# ir.net
KiCad netlist of a schematic drawn in EAGLE
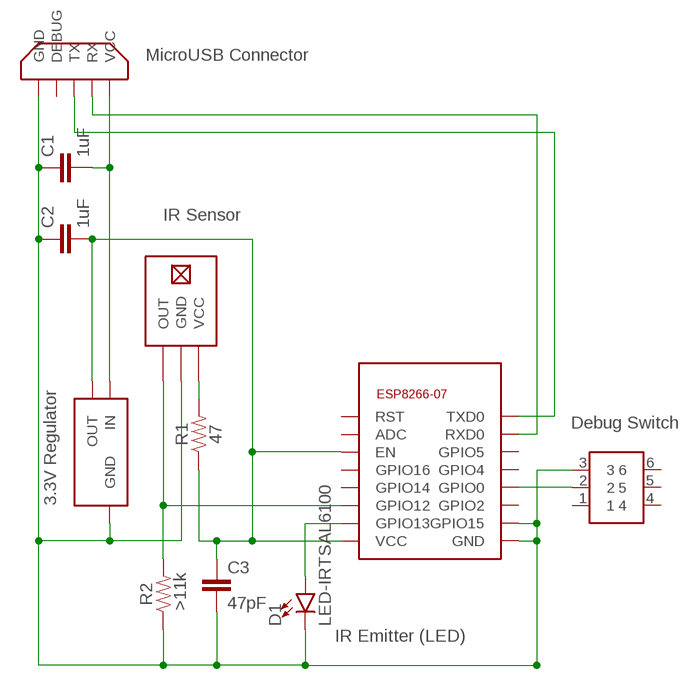
[diagram p0: schematic, sheet 1]

(export (version "E")
  (design (tool "Eeschema 10.0.6"))
  (components
    (comp (ref "C1")
      (value "1uF")
      (footprint "eagle-import:0805")
      (libsource (lib "eagle-import") (part "0.33UF/330NF-0805-50V-10%"))
    )
    (comp (ref "C2")
      (value "1uF")
      (footprint "eagle-import:0805")
      (libsource (lib "eagle-import") (part "0.33UF/330NF-0805-50V-10%"))
    )
    (comp (ref "C3")
      (value "47pF")
      (footprint "eagle-import:0805")
      (libsource (lib "eagle-import") (part "0.33UF/330NF-0805-50V-10%"))
    )
    (comp (ref "D1")
      (value "LED-IRTSAL6100")
      (footprint "eagle-import:LED_5MM")
      (libsource (lib "eagle-import") (part "LED-IRTSAL6100"))
    )
    (comp (ref "R1")
      (value "47")
      (footprint "eagle-import:0805")
      (libsource (lib "eagle-import") (part "RESISTOR0805"))
    )
    (comp (ref "R2")
      (value ">11k")
      (footprint "eagle-import:0805")
      (libsource (lib "eagle-import") (part "RESISTOR0805"))
    )
    (comp (ref "U$1")
      (value "AX-1838HSHORIZ")
      (footprint "eagle-import:AX-1838HS-HORIZ")
      (libsource (lib "eagle-import") (part "AX-1838HSHORIZ"))
    )
    (comp (ref "U$2")
      (value "ESP8266-07SMD")
      (footprint "eagle-import:ESP8266-07")
      (libsource (lib "eagle-import") (part "ESP8266-07SMD"))
    )
    (comp (ref "U$3")
      (value "AYZ0202AGRL")
      (footprint "eagle-import:AYZ0202AGRL")
      (libsource (lib "eagle-import") (part "AYZ0202AGRL"))
    )
    (comp (ref "U$4")
      (value "MICROUSB609-4613-1-ND")
      (footprint "eagle-import:MICROUSB")
      (libsource (lib "eagle-import") (part "MICROUSB609-4613-1-ND"))
    )
    (comp (ref "U$5")
      (value "AZ1117E")
      (footprint "eagle-import:SOT-223")
      (libsource (lib "eagle-import") (part "AZ1117E"))
    )
  )
  (nets
    (net (code "1") (name "Net-(C2-Pad2)") (class "Default")
      (node (ref "C2") (pin "2") (pinfunction "2_2") (pintype "passive"))
      (node (ref "C3") (pin "1") (pinfunction "1_1") (pintype "passive"))
      (node (ref "R1") (pin "1") (pinfunction "1_1") (pintype "passive"))
      (node (ref "U$2") (pin "EN") (pinfunction "EN_EN") (pintype "input"))
      (node (ref "U$2") (pin "VCC") (pinfunction "VCC_VCC") (pintype "power_in"))
      (node (ref "U$5") (pin "P$1") (pinfunction "OUT_P$1") (pintype "output"))
      (node (ref "U$5") (pin "P$2") (pinfunction "OUT_P$2") (pintype "output"))
    )
    (net (code "2") (name "Net-(D1-C)") (class "Default")
      (node (ref "C1") (pin "1") (pinfunction "1_1") (pintype "passive"))
      (node (ref "C2") (pin "1") (pinfunction "1_1") (pintype "passive"))
      (node (ref "C3") (pin "2") (pinfunction "2_2") (pintype "passive"))
      (node (ref "D1") (pin "K") (pinfunction "C_K") (pintype "passive"))
      (node (ref "R2") (pin "1") (pinfunction "1_1") (pintype "passive"))
      (node (ref "U$1") (pin "GND") (pinfunction "GND_GND") (pintype "power_in"))
      (node (ref "U$2") (pin "GND") (pinfunction "GND_GND") (pintype "power_in"))
      (node (ref "U$2") (pin "GPIO15") (pinfunction "GPIO15_GPIO15") (pintype "bidirectional"))
      (node (ref "U$3") (pin "3") (pinfunction "3_3") (pintype "bidirectional"))
      (node (ref "U$4") (pin "GND") (pinfunction "GND_GND") (pintype "power_in"))
      (node (ref "U$5") (pin "P$3") (pinfunction "GND_P$3") (pintype "power_in"))
    )
    (net (code "3") (name "Net-(D1-PadA)") (class "Default")
      (node (ref "D1") (pin "A") (pinfunction "A_A") (pintype "passive"))
      (node (ref "U$2") (pin "GPIO13") (pinfunction "GPIO13_GPIO13") (pintype "bidirectional"))
    )
    (net (code "4") (name "Net-(R1-Pad2)") (class "Default")
      (node (ref "R1") (pin "2") (pinfunction "2_2") (pintype "passive"))
      (node (ref "U$1") (pin "VCC") (pinfunction "VCC_VCC") (pintype "power_in"))
    )
    (net (code "5") (name "Net-(R2-Pad2)") (class "Default")
      (node (ref "R2") (pin "2") (pinfunction "2_2") (pintype "passive"))
      (node (ref "U$1") (pin "OUT") (pinfunction "OUT_OUT") (pintype "bidirectional"))
      (node (ref "U$2") (pin "GPIO12") (pinfunction "GPIO12_GPIO12") (pintype "bidirectional"))
    )
    (net (code "6") (name "Net-(U$2-PadGPIO0)") (class "Default")
      (node (ref "U$2") (pin "GPIO0") (pinfunction "GPIO0_GPIO0") (pintype "bidirectional"))
      (node (ref "U$3") (pin "2") (pinfunction "2_2") (pintype "bidirectional"))
    )
    (net (code "7") (name "Net-(U$2-PadRXD0)") (class "Default")
      (node (ref "U$2") (pin "RXD0") (pinfunction "RXD0_RXD0") (pintype "bidirectional"))
      (node (ref "U$4") (pin "RX") (pinfunction "RX_RX") (pintype "bidirectional"))
    )
    (net (code "8") (name "Net-(U$2-PadTXD0)") (class "Default")
      (node (ref "U$2") (pin "TXD0") (pinfunction "TXD0_TXD0") (pintype "bidirectional"))
      (node (ref "U$4") (pin "TX") (pinfunction "TX_TX") (pintype "bidirectional"))
    )
    (net (code "9") (name "Net-(U$5-IN)") (class "Default")
      (node (ref "C1") (pin "2") (pinfunction "2_2") (pintype "passive"))
      (node (ref "U$4") (pin "VCC") (pinfunction "VCC_VCC") (pintype "power_in"))
      (node (ref "U$5") (pin "P$4") (pinfunction "IN_P$4") (pintype "input"))
    )
    (net (code "10") (name "unconnected-(U$2-PadADC)") (class "Default")
      (node (ref "U$2") (pin "ADC") (pinfunction "ADC_ADC") (pintype "input"))
    )
    (net (code "11") (name "unconnected-(U$2-PadGPIO2)") (class "Default")
      (node (ref "U$2") (pin "GPIO2") (pinfunction "GPIO2_GPIO2") (pintype "bidirectional"))
    )
    (net (code "12") (name "unconnected-(U$2-PadGPIO4)") (class "Default")
      (node (ref "U$2") (pin "GPIO4") (pinfunction "GPIO4_GPIO4") (pintype "bidirectional"))
    )
    (net (code "13") (name "unconnected-(U$2-PadGPIO5)") (class "Default")
      (node (ref "U$2") (pin "GPIO5") (pinfunction "GPIO5_GPIO5") (pintype "bidirectional"))
    )
    (net (code "14") (name "unconnected-(U$2-PadGPIO14)") (class "Default")
      (node (ref "U$2") (pin "GPIO14") (pinfunction "GPIO14_GPIO14") (pintype "bidirectional"))
    )
    (net (code "15") (name "unconnected-(U$2-PadGPIO16)") (class "Default")
      (node (ref "U$2") (pin "GPIO16") (pinfunction "GPIO16_GPIO16") (pintype "bidirectional"))
    )
    (net (code "16") (name "unconnected-(U$2-PadRST)") (class "Default")
      (node (ref "U$2") (pin "RST") (pinfunction "RST_RST") (pintype "input"))
    )
    (net (code "17") (name "unconnected-(U$3-Pad1)") (class "Default")
      (node (ref "U$3") (pin "1") (pinfunction "1_1") (pintype "bidirectional"))
    )
    (net (code "18") (name "unconnected-(U$3-Pad4)") (class "Default")
      (node (ref "U$3") (pin "4") (pinfunction "4_4") (pintype "bidirectional"))
    )
    (net (code "19") (name "unconnected-(U$3-Pad5)") (class "Default")
      (node (ref "U$3") (pin "5") (pinfunction "5_5") (pintype "bidirectional"))
    )
    (net (code "20") (name "unconnected-(U$3-Pad6)") (class "Default")
      (node (ref "U$3") (pin "6") (pinfunction "6_6") (pintype "bidirectional"))
    )
    (net (code "21") (name "unconnected-(U$4-PadDEBUG)") (class "Default")
      (node (ref "U$4") (pin "DEBUG") (pinfunction "DEBUG_DEBUG") (pintype "bidirectional"))
    )
  )
)
